# DAC_Zmatching.net
KiCad netlist of a schematic drawn in Altium Designer
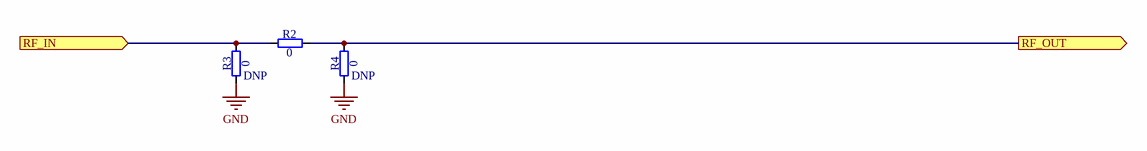
[diagram p0: DAC_Zmatching.SchDoc]

(export (version "E")
  (design (tool "Eeschema 10.0.6"))
  (components
    (comp (ref "R2")
      (value "0")
      (footprint "RESC1005X40N")
      (description "Resistor")
      (fields
        (field (name "PART NUMBER") "R0402_0R_JUMPER")
        (field (name "MANUFACTURER") "GENERIC")
        (field (name "AUTHOR") "CERN DEM JLC")
      )
      (libsource (lib "Resistors") (part "Resistor"))
    )
    (comp (ref "R3")
      (value "0")
      (footprint "RESC1005X40N")
      (description "Resistor")
      (fields
        (field (name "PART NUMBER") "R0402_0R_JUMPER")
        (field (name "MANUFACTURER") "GENERIC")
        (field (name "MOUNTED") "DNP")
        (field (name "AUTHOR") "CERN DEM JLC")
      )
      (libsource (lib "Resistors") (part "Resistor"))
    )
    (comp (ref "R4")
      (value "0")
      (footprint "RESC1005X40N")
      (description "Resistor")
      (fields
        (field (name "PART NUMBER") "R0402_0R_JUMPER")
        (field (name "MANUFACTURER") "GENERIC")
        (field (name "MOUNTED") "DNP")
        (field (name "AUTHOR") "CERN DEM JLC")
      )
      (libsource (lib "Resistors") (part "Resistor"))
    )
  )
  (nets
    (net (code "1") (name "/RF_IN") (class "Default")
      (node (ref "R2") (pin "1") (pinfunction "1_1") (pintype "passive"))
      (node (ref "R3") (pin "2") (pinfunction "2_2") (pintype "passive"))
    )
    (net (code "2") (name "/RF_OUT") (class "Default")
      (node (ref "R2") (pin "2") (pinfunction "2_2") (pintype "passive"))
      (node (ref "R4") (pin "2") (pinfunction "2_2") (pintype "passive"))
    )
    (net (code "3") (name "GND") (class "Default")
      (node (ref "R3") (pin "1") (pinfunction "1_1") (pintype "passive"))
      (node (ref "R4") (pin "1") (pinfunction "1_1") (pintype "passive"))
    )
  )
)
